# TopSchem.net
KiCad netlist of a schematic drawn in EAGLE
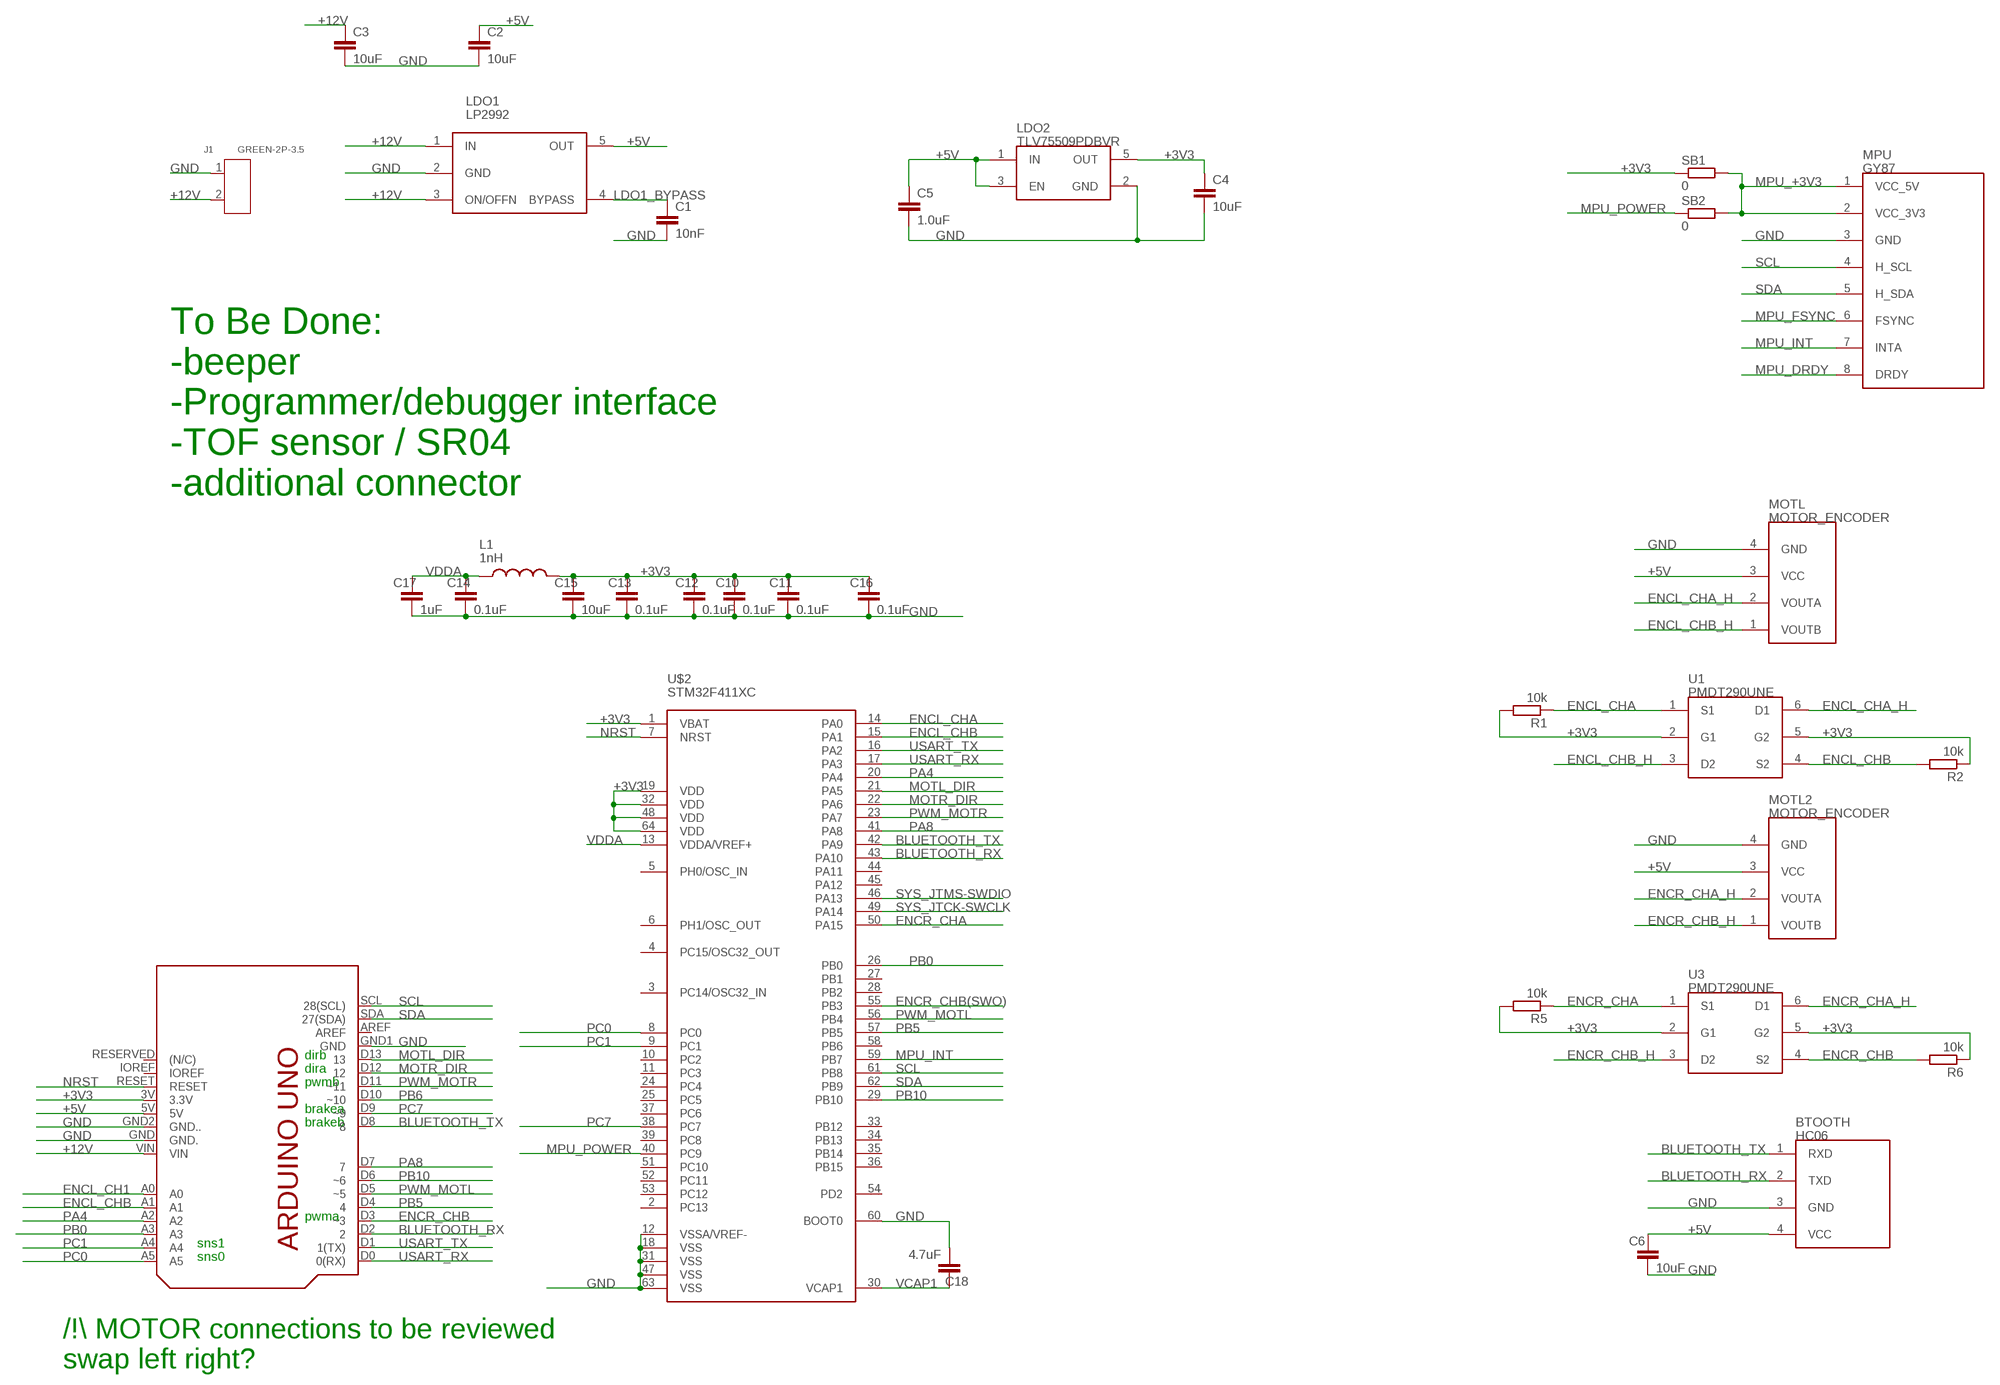
[diagram p0: schematic, sheet 1]

(export (version "E")
  (design (tool "Eeschema 10.0.6"))
  (components
    (comp (ref "BTOOTH")
      (value "HC06")
      (footprint "eagle-import:HC06")
      (libsource (lib "eagle-import") (part "HC06HC06"))
    )
    (comp (ref "C1")
      (value "10nF")
      (footprint "eagle-import:0603")
      (libsource (lib "eagle-import") (part "10NF-0603-50V-10%"))
    )
    (comp (ref "C2")
      (value "10uF")
      (footprint "eagle-import:0603")
      (libsource (lib "eagle-import") (part "10UF-0603-6.3V-20%"))
    )
    (comp (ref "C3")
      (value "10uF")
      (footprint "eagle-import:0603")
      (libsource (lib "eagle-import") (part "10UF-0603-6.3V-20%"))
    )
    (comp (ref "C4")
      (value "10uF")
      (footprint "eagle-import:0603")
      (libsource (lib "eagle-import") (part "10UF-0603-6.3V-20%"))
    )
    (comp (ref "C5")
      (value "1.0uF")
      (footprint "eagle-import:0603")
      (libsource (lib "eagle-import") (part "1.0UF-0603-16V-10%"))
    )
    (comp (ref "C6")
      (value "10uF")
      (footprint "eagle-import:0603")
      (libsource (lib "eagle-import") (part "0.1UF-0603-25V-(+80/-20%)"))
    )
    (comp (ref "C10")
      (value "0.1uF")
      (footprint "eagle-import:0603")
      (libsource (lib "eagle-import") (part "0.1UF-0603-25V-(+80/-20%)"))
    )
    (comp (ref "C11")
      (value "0.1uF")
      (footprint "eagle-import:0603")
      (libsource (lib "eagle-import") (part "0.1UF-0603-25V-(+80/-20%)"))
    )
    (comp (ref "C12")
      (value "0.1uF")
      (footprint "eagle-import:0603")
      (libsource (lib "eagle-import") (part "0.1UF-0603-25V-(+80/-20%)"))
    )
    (comp (ref "C13")
      (value "0.1uF")
      (footprint "eagle-import:0603")
      (libsource (lib "eagle-import") (part "0.1UF-0603-25V-(+80/-20%)"))
    )
    (comp (ref "C14")
      (value "0.1uF")
      (footprint "eagle-import:0603")
      (libsource (lib "eagle-import") (part "0.1UF-0603-25V-(+80/-20%)"))
    )
    (comp (ref "C15")
      (value "10uF")
      (footprint "eagle-import:0603")
      (libsource (lib "eagle-import") (part "0.1UF-0603-25V-(+80/-20%)"))
    )
    (comp (ref "C16")
      (value "0.1uF")
      (footprint "eagle-import:0603")
      (libsource (lib "eagle-import") (part "0.1UF-0603-25V-(+80/-20%)"))
    )
    (comp (ref "C17")
      (value "1uF")
      (footprint "eagle-import:0603")
      (libsource (lib "eagle-import") (part "0.1UF-0603-25V-(+80/-20%)"))
    )
    (comp (ref "C18")
      (value "4.7uF")
      (footprint "eagle-import:0603")
      (libsource (lib "eagle-import") (part "0.1UF-0603-25V-(+80/-20%)"))
    )
    (comp (ref "J1")
      (value "GREEN-2P-3.5")
      (footprint "eagle-import:H2-3.5-7.0X7.0MM")
      (libsource (lib "eagle-import") (part "SCREW-TERMINAL-GREEN(2P-3.5)"))
    )
    (comp (ref "L1")
      (value "1nH")
      (footprint "eagle-import:C0603")
      (libsource (lib "eagle-import") (part "INDUCTORC0603"))
    )
    (comp (ref "LDO1")
      (value "LP2992")
      (footprint "eagle-import:WE-TVS_SOT23-5L")
      (libsource (lib "eagle-import") (part "LP2992SOT23-5L"))
    )
    (comp (ref "LDO2")
      (value "TLV75509PDBVR")
      (footprint "eagle-import:WE-TVS_SOT23-5L")
      (libsource (lib "eagle-import") (part "TLV755P"))
    )
    (comp (ref "MOTL")
      (value "MOTOR_ENCODER")
      (footprint "eagle-import:ENCODER")
      (libsource (lib "eagle-import") (part "MOTOR_ENCODER"))
    )
    (comp (ref "MOTL2")
      (value "MOTOR_ENCODER")
      (footprint "eagle-import:ENCODER")
      (libsource (lib "eagle-import") (part "MOTOR_ENCODER"))
    )
    (comp (ref "MPU")
      (value "GY87")
      (footprint "eagle-import:SIP8")
      (libsource (lib "eagle-import") (part "GY87GY87"))
    )
    (comp (ref "R1")
      (value "10k")
      (footprint "eagle-import:R0603")
      (libsource (lib "eagle-import") (part "R-EU_R0603"))
    )
    (comp (ref "R2")
      (value "10k")
      (footprint "eagle-import:R0603")
      (libsource (lib "eagle-import") (part "R-EU_R0603"))
    )
    (comp (ref "R5")
      (value "10k")
      (footprint "eagle-import:R0603")
      (libsource (lib "eagle-import") (part "R-EU_R0603"))
    )
    (comp (ref "R6")
      (value "10k")
      (footprint "eagle-import:R0603")
      (libsource (lib "eagle-import") (part "R-EU_R0603"))
    )
    (comp (ref "SB1")
      (value "0")
      (footprint "eagle-import:R0603")
      (libsource (lib "eagle-import") (part "R-EU_R0603"))
    )
    (comp (ref "SB2")
      (value "0")
      (footprint "eagle-import:R0603")
      (libsource (lib "eagle-import") (part "R-EU_R0603"))
    )
    (comp (ref "SHIELD")
      (value "ARDUINO_UNO_EXTARDUINO_R3")
      (footprint "eagle-import:ARDUINOR3")
      (libsource (lib "eagle-import") (part "ARDUINO_UNO_EXTARDUINO_R3"))
    )
    (comp (ref "U$2")
      (value "STM32F411XC")
      (footprint "eagle-import:LQFP64")
      (libsource (lib "eagle-import") (part "STM32F411XC"))
    )
    (comp (ref "U1")
      (value "PMDT290UNE")
      (footprint "eagle-import:SOT666")
      (libsource (lib "eagle-import") (part "PMDT290UNESOT666"))
    )
    (comp (ref "U3")
      (value "PMDT290UNE")
      (footprint "eagle-import:SOT666")
      (libsource (lib "eagle-import") (part "PMDT290UNESOT666"))
    )
  )
  (nets
    (net (code "1") (name "/+3V3") (class "Default")
      (node (ref "C10") (pin "1") (pinfunction "1_1") (pintype "passive"))
      (node (ref "C11") (pin "1") (pinfunction "1_1") (pintype "passive"))
      (node (ref "C12") (pin "1") (pinfunction "1_1") (pintype "passive"))
      (node (ref "C13") (pin "1") (pinfunction "1_1") (pintype "passive"))
      (node (ref "C15") (pin "1") (pinfunction "1_1") (pintype "passive"))
      (node (ref "C16") (pin "1") (pinfunction "1_1") (pintype "passive"))
      (node (ref "C4") (pin "1") (pinfunction "1_1") (pintype "passive"))
      (node (ref "L1") (pin "2") (pinfunction "2_2") (pintype "passive"))
      (node (ref "LDO2") (pin "5") (pinfunction "OUT_5") (pintype "power_in"))
      (node (ref "R1") (pin "2") (pinfunction "2_2") (pintype "passive"))
      (node (ref "R2") (pin "1") (pinfunction "1_1") (pintype "passive"))
      (node (ref "R5") (pin "2") (pinfunction "2_2") (pintype "passive"))
      (node (ref "R6") (pin "1") (pinfunction "1_1") (pintype "passive"))
      (node (ref "SB1") (pin "1") (pinfunction "1_1") (pintype "passive"))
      (node (ref "SHIELD") (pin "3V") (pinfunction "3.3V_3V") (pintype "bidirectional"))
      (node (ref "U$2") (pin "1") (pinfunction "VBAT_1") (pintype "bidirectional"))
      (node (ref "U$2") (pin "19") (pinfunction "VDD_19") (pintype "bidirectional"))
      (node (ref "U$2") (pin "32") (pinfunction "VDD_32") (pintype "bidirectional"))
      (node (ref "U$2") (pin "48") (pinfunction "VDD_48") (pintype "bidirectional"))
      (node (ref "U$2") (pin "64") (pinfunction "VDD_64") (pintype "bidirectional"))
      (node (ref "U1") (pin "2") (pinfunction "G1_2") (pintype "input"))
      (node (ref "U1") (pin "5") (pinfunction "G2_5") (pintype "input"))
      (node (ref "U3") (pin "2") (pinfunction "G1_2") (pintype "input"))
      (node (ref "U3") (pin "5") (pinfunction "G2_5") (pintype "input"))
    )
    (net (code "2") (name "/+5V") (class "Default")
      (node (ref "BTOOTH") (pin "4") (pinfunction "VCC_4") (pintype "power_in"))
      (node (ref "C2") (pin "1") (pinfunction "1_1") (pintype "passive"))
      (node (ref "C5") (pin "1") (pinfunction "1_1") (pintype "passive"))
      (node (ref "C6") (pin "1") (pinfunction "1_1") (pintype "passive"))
      (node (ref "LDO1") (pin "5") (pinfunction "OUT_5") (pintype "power_in"))
      (node (ref "LDO2") (pin "1") (pinfunction "IN_1") (pintype "power_in"))
      (node (ref "LDO2") (pin "3") (pinfunction "EN_3") (pintype "input"))
      (node (ref "MOTL") (pin "3") (pinfunction "VCC_3") (pintype "power_in"))
      (node (ref "MOTL2") (pin "3") (pinfunction "VCC_3") (pintype "power_in"))
      (node (ref "SHIELD") (pin "5V") (pinfunction "5V_5V") (pintype "bidirectional"))
    )
    (net (code "3") (name "/+12V") (class "Default")
      (node (ref "C3") (pin "1") (pinfunction "1_1") (pintype "passive"))
      (node (ref "J1") (pin "2") (pinfunction "2_2") (pintype "bidirectional"))
      (node (ref "LDO1") (pin "1") (pinfunction "IN_1") (pintype "power_in"))
      (node (ref "LDO1") (pin "3") (pinfunction "ON/OFFN_3") (pintype "input"))
      (node (ref "SHIELD") (pin "VIN") (pinfunction "VIN_VIN") (pintype "bidirectional"))
    )
    (net (code "4") (name "/BLUETOOTH_RX") (class "Default")
      (node (ref "BTOOTH") (pin "2") (pinfunction "TXD_2") (pintype "input"))
      (node (ref "SHIELD") (pin "D2") (pinfunction "2_D2") (pintype "bidirectional"))
      (node (ref "U$2") (pin "43") (pinfunction "PA10_43") (pintype "bidirectional"))
    )
    (net (code "5") (name "/BLUETOOTH_TX") (class "Default")
      (node (ref "BTOOTH") (pin "1") (pinfunction "RXD_1") (pintype "output"))
      (node (ref "SHIELD") (pin "D8") (pinfunction "8_D8") (pintype "bidirectional"))
      (node (ref "U$2") (pin "42") (pinfunction "PA9_42") (pintype "bidirectional"))
    )
    (net (code "6") (name "/ENCL_CH1") (class "Default")
      (node (ref "SHIELD") (pin "A0") (pinfunction "A0_A0") (pintype "bidirectional"))
    )
    (net (code "7") (name "/ENCL_CHA") (class "Default")
      (node (ref "R1") (pin "1") (pinfunction "1_1") (pintype "passive"))
      (node (ref "U$2") (pin "14") (pinfunction "PA0_14") (pintype "bidirectional"))
      (node (ref "U1") (pin "1") (pinfunction "S1_1") (pintype "bidirectional"))
    )
    (net (code "8") (name "/ENCL_CHA_H") (class "Default")
      (node (ref "MOTL") (pin "2") (pinfunction "VOUTA_2") (pintype "bidirectional"))
      (node (ref "U1") (pin "6") (pinfunction "D1_6") (pintype "bidirectional"))
    )
    (net (code "9") (name "/ENCL_CHB") (class "Default")
      (node (ref "R2") (pin "2") (pinfunction "2_2") (pintype "passive"))
      (node (ref "SHIELD") (pin "A1") (pinfunction "A1_A1") (pintype "bidirectional"))
      (node (ref "U$2") (pin "15") (pinfunction "PA1_15") (pintype "bidirectional"))
      (node (ref "U1") (pin "4") (pinfunction "S2_4") (pintype "bidirectional"))
    )
    (net (code "10") (name "/ENCL_CHB_H") (class "Default")
      (node (ref "MOTL") (pin "1") (pinfunction "VOUTB_1") (pintype "bidirectional"))
      (node (ref "U1") (pin "3") (pinfunction "D2_3") (pintype "bidirectional"))
    )
    (net (code "11") (name "/ENCR_CHA") (class "Default")
      (node (ref "R5") (pin "1") (pinfunction "1_1") (pintype "passive"))
      (node (ref "U$2") (pin "50") (pinfunction "PA15_50") (pintype "bidirectional"))
      (node (ref "U3") (pin "1") (pinfunction "S1_1") (pintype "bidirectional"))
    )
    (net (code "12") (name "/ENCR_CHA_H") (class "Default")
      (node (ref "MOTL2") (pin "2") (pinfunction "VOUTA_2") (pintype "bidirectional"))
      (node (ref "U3") (pin "6") (pinfunction "D1_6") (pintype "bidirectional"))
    )
    (net (code "13") (name "/ENCR_CHB") (class "Default")
      (node (ref "R6") (pin "2") (pinfunction "2_2") (pintype "passive"))
      (node (ref "SHIELD") (pin "D3") (pinfunction "~{3}_D3") (pintype "bidirectional"))
      (node (ref "U3") (pin "4") (pinfunction "S2_4") (pintype "bidirectional"))
    )
    (net (code "14") (name "/ENCR_CHB(SWO)") (class "Default")
      (node (ref "U$2") (pin "55") (pinfunction "PB3_55") (pintype "bidirectional"))
    )
    (net (code "15") (name "/ENCR_CHB_H") (class "Default")
      (node (ref "MOTL2") (pin "1") (pinfunction "VOUTB_1") (pintype "bidirectional"))
      (node (ref "U3") (pin "3") (pinfunction "D2_3") (pintype "bidirectional"))
    )
    (net (code "16") (name "/GND") (class "Default")
      (node (ref "BTOOTH") (pin "3") (pinfunction "GND_3") (pintype "power_in"))
      (node (ref "C1") (pin "2") (pinfunction "2_2") (pintype "passive"))
      (node (ref "C10") (pin "2") (pinfunction "2_2") (pintype "passive"))
      (node (ref "C11") (pin "2") (pinfunction "2_2") (pintype "passive"))
      (node (ref "C12") (pin "2") (pinfunction "2_2") (pintype "passive"))
      (node (ref "C13") (pin "2") (pinfunction "2_2") (pintype "passive"))
      (node (ref "C14") (pin "2") (pinfunction "2_2") (pintype "passive"))
      (node (ref "C15") (pin "2") (pinfunction "2_2") (pintype "passive"))
      (node (ref "C16") (pin "2") (pinfunction "2_2") (pintype "passive"))
      (node (ref "C17") (pin "2") (pinfunction "2_2") (pintype "passive"))
      (node (ref "C18") (pin "2") (pinfunction "2_2") (pintype "passive"))
      (node (ref "C2") (pin "2") (pinfunction "2_2") (pintype "passive"))
      (node (ref "C3") (pin "2") (pinfunction "2_2") (pintype "passive"))
      (node (ref "C4") (pin "2") (pinfunction "2_2") (pintype "passive"))
      (node (ref "C5") (pin "2") (pinfunction "2_2") (pintype "passive"))
      (node (ref "C6") (pin "2") (pinfunction "2_2") (pintype "passive"))
      (node (ref "J1") (pin "1") (pinfunction "1_1") (pintype "bidirectional"))
      (node (ref "LDO1") (pin "2") (pinfunction "GND_2") (pintype "power_in"))
      (node (ref "LDO2") (pin "2") (pinfunction "GND_2") (pintype "power_in"))
      (node (ref "MOTL") (pin "4") (pinfunction "GND_4") (pintype "power_in"))
      (node (ref "MOTL2") (pin "4") (pinfunction "GND_4") (pintype "power_in"))
      (node (ref "MPU") (pin "3") (pinfunction "GND_3") (pintype "power_in"))
      (node (ref "SHIELD") (pin "GND") (pinfunction "GND._GND") (pintype "bidirectional"))
      (node (ref "SHIELD") (pin "GND1") (pinfunction "GND_GND1") (pintype "bidirectional"))
      (node (ref "SHIELD") (pin "GND2") (pinfunction "GND.._GND2") (pintype "bidirectional"))
      (node (ref "U$2") (pin "12") (pinfunction "VSSA/VREF-_12") (pintype "bidirectional"))
      (node (ref "U$2") (pin "18") (pinfunction "VSS_18") (pintype "bidirectional"))
      (node (ref "U$2") (pin "31") (pinfunction "VSS_31") (pintype "bidirectional"))
      (node (ref "U$2") (pin "47") (pinfunction "VSS_47") (pintype "bidirectional"))
      (node (ref "U$2") (pin "60") (pinfunction "BOOT0_60") (pintype "bidirectional"))
      (node (ref "U$2") (pin "63") (pinfunction "VSS_63") (pintype "bidirectional"))
    )
    (net (code "17") (name "/LDO1_BYPASS") (class "Default")
      (node (ref "C1") (pin "1") (pinfunction "1_1") (pintype "passive"))
      (node (ref "LDO1") (pin "4") (pinfunction "BYPASS_4") (pintype "output"))
    )
    (net (code "18") (name "/MOTL_DIR") (class "Default")
      (node (ref "SHIELD") (pin "D13") (pinfunction "13_D13") (pintype "bidirectional"))
      (node (ref "U$2") (pin "21") (pinfunction "PA5_21") (pintype "bidirectional"))
    )
    (net (code "19") (name "/MOTR_DIR") (class "Default")
      (node (ref "SHIELD") (pin "D12") (pinfunction "12_D12") (pintype "bidirectional"))
      (node (ref "U$2") (pin "22") (pinfunction "PA6_22") (pintype "bidirectional"))
    )
    (net (code "20") (name "/MPU_+3V3") (class "Default")
      (node (ref "MPU") (pin "1") (pinfunction "VCC_5V_1") (pintype "power_in"))
      (node (ref "MPU") (pin "2") (pinfunction "VCC_3V3_2") (pintype "power_in"))
      (node (ref "SB1") (pin "2") (pinfunction "2_2") (pintype "passive"))
      (node (ref "SB2") (pin "2") (pinfunction "2_2") (pintype "passive"))
    )
    (net (code "21") (name "/MPU_DRDY") (class "Default")
      (node (ref "MPU") (pin "8") (pinfunction "DRDY_8") (pintype "bidirectional"))
    )
    (net (code "22") (name "/MPU_FSYNC") (class "Default")
      (node (ref "MPU") (pin "6") (pinfunction "FSYNC_6") (pintype "bidirectional"))
    )
    (net (code "23") (name "/MPU_INT") (class "Default")
      (node (ref "MPU") (pin "7") (pinfunction "INTA_7") (pintype "bidirectional"))
      (node (ref "U$2") (pin "59") (pinfunction "PB7_59") (pintype "bidirectional"))
    )
    (net (code "24") (name "/MPU_POWER") (class "Default")
      (node (ref "SB2") (pin "1") (pinfunction "1_1") (pintype "passive"))
      (node (ref "U$2") (pin "40") (pinfunction "PC9_40") (pintype "bidirectional"))
    )
    (net (code "25") (name "/NRST") (class "Default")
      (node (ref "SHIELD") (pin "RESET") (pinfunction "RESET_RESET") (pintype "bidirectional"))
      (node (ref "U$2") (pin "7") (pinfunction "NRST_7") (pintype "bidirectional"))
    )
    (net (code "26") (name "/PA4") (class "Default")
      (node (ref "SHIELD") (pin "A2") (pinfunction "A2_A2") (pintype "bidirectional"))
      (node (ref "U$2") (pin "20") (pinfunction "PA4_20") (pintype "bidirectional"))
    )
    (net (code "27") (name "/PA8") (class "Default")
      (node (ref "SHIELD") (pin "D7") (pinfunction "7_D7") (pintype "bidirectional"))
      (node (ref "U$2") (pin "41") (pinfunction "PA8_41") (pintype "bidirectional"))
    )
    (net (code "28") (name "/PB0") (class "Default")
      (node (ref "SHIELD") (pin "A3") (pinfunction "A3_A3") (pintype "bidirectional"))
      (node (ref "U$2") (pin "26") (pinfunction "PB0_26") (pintype "bidirectional"))
    )
    (net (code "29") (name "/PB5") (class "Default")
      (node (ref "SHIELD") (pin "D4") (pinfunction "4_D4") (pintype "bidirectional"))
      (node (ref "U$2") (pin "57") (pinfunction "PB5_57") (pintype "bidirectional"))
    )
    (net (code "30") (name "/PB6") (class "Default")
      (node (ref "SHIELD") (pin "D10") (pinfunction "~{10}_D10") (pintype "bidirectional"))
    )
    (net (code "31") (name "/PB10") (class "Default")
      (node (ref "SHIELD") (pin "D6") (pinfunction "~{6}_D6") (pintype "bidirectional"))
      (node (ref "U$2") (pin "29") (pinfunction "PB10_29") (pintype "bidirectional"))
    )
    (net (code "32") (name "/PC0") (class "Default")
      (node (ref "SHIELD") (pin "A5") (pinfunction "A5_A5") (pintype "bidirectional"))
      (node (ref "U$2") (pin "8") (pinfunction "PC0_8") (pintype "bidirectional"))
    )
    (net (code "33") (name "/PC1") (class "Default")
      (node (ref "SHIELD") (pin "A4") (pinfunction "A4_A4") (pintype "bidirectional"))
      (node (ref "U$2") (pin "9") (pinfunction "PC1_9") (pintype "bidirectional"))
    )
    (net (code "34") (name "/PC7") (class "Default")
      (node (ref "SHIELD") (pin "D9") (pinfunction "~{9}_D9") (pintype "bidirectional"))
      (node (ref "U$2") (pin "38") (pinfunction "PC7_38") (pintype "bidirectional"))
    )
    (net (code "35") (name "/PWM_MOTL") (class "Default")
      (node (ref "SHIELD") (pin "D5") (pinfunction "~{5}_D5") (pintype "bidirectional"))
      (node (ref "U$2") (pin "56") (pinfunction "PB4_56") (pintype "bidirectional"))
    )
    (net (code "36") (name "/PWM_MOTR") (class "Default")
      (node (ref "SHIELD") (pin "D11") (pinfunction "~{11}_D11") (pintype "bidirectional"))
      (node (ref "U$2") (pin "23") (pinfunction "PA7_23") (pintype "bidirectional"))
    )
    (net (code "37") (name "/SCL") (class "Default")
      (node (ref "MPU") (pin "4") (pinfunction "H_SCL_4") (pintype "bidirectional"))
      (node (ref "SHIELD") (pin "SCL") (pinfunction "28(SCL)_SCL") (pintype "bidirectional"))
      (node (ref "U$2") (pin "61") (pinfunction "PB8_61") (pintype "bidirectional"))
    )
    (net (code "38") (name "/SDA") (class "Default")
      (node (ref "MPU") (pin "5") (pinfunction "H_SDA_5") (pintype "bidirectional"))
      (node (ref "SHIELD") (pin "SDA") (pinfunction "27(SDA)_SDA") (pintype "bidirectional"))
      (node (ref "U$2") (pin "62") (pinfunction "PB9_62") (pintype "bidirectional"))
    )
    (net (code "39") (name "/SYS_JTCK-SWCLK") (class "Default")
      (node (ref "U$2") (pin "49") (pinfunction "PA14_49") (pintype "bidirectional"))
    )
    (net (code "40") (name "/SYS_JTMS-SWDIO") (class "Default")
      (node (ref "U$2") (pin "46") (pinfunction "PA13_46") (pintype "bidirectional"))
    )
    (net (code "41") (name "/USART_RX") (class "Default")
      (node (ref "SHIELD") (pin "D0") (pinfunction "0(RX)_D0") (pintype "bidirectional"))
      (node (ref "U$2") (pin "17") (pinfunction "PA3_17") (pintype "bidirectional"))
    )
    (net (code "42") (name "/USART_TX") (class "Default")
      (node (ref "SHIELD") (pin "D1") (pinfunction "1(TX)_D1") (pintype "bidirectional"))
      (node (ref "U$2") (pin "16") (pinfunction "PA2_16") (pintype "bidirectional"))
    )
    (net (code "43") (name "/VCAP1") (class "Default")
      (node (ref "C18") (pin "1") (pinfunction "1_1") (pintype "passive"))
      (node (ref "U$2") (pin "30") (pinfunction "VCAP1_30") (pintype "bidirectional"))
    )
    (net (code "44") (name "/VDDA") (class "Default")
      (node (ref "C14") (pin "1") (pinfunction "1_1") (pintype "passive"))
      (node (ref "C17") (pin "1") (pinfunction "1_1") (pintype "passive"))
      (node (ref "L1") (pin "1") (pinfunction "1_1") (pintype "passive"))
      (node (ref "U$2") (pin "13") (pinfunction "VDDA/VREF+_13") (pintype "bidirectional"))
    )
    (net (code "45") (name "unconnected-(SHIELD-(N{slash}C)-PadRESERVED)") (class "Default")
      (node (ref "SHIELD") (pin "RESERVED") (pinfunction "(N/C)_RESERVED") (pintype "bidirectional"))
    )
    (net (code "46") (name "unconnected-(SHIELD-PadAREF)") (class "Default")
      (node (ref "SHIELD") (pin "AREF") (pinfunction "AREF_AREF") (pintype "bidirectional"))
    )
    (net (code "47") (name "unconnected-(SHIELD-PadIOREF)") (class "Default")
      (node (ref "SHIELD") (pin "IOREF") (pinfunction "IOREF_IOREF") (pintype "bidirectional"))
    )
    (net (code "48") (name "unconnected-(U$2-PA11-Pad44)") (class "Default")
      (node (ref "U$2") (pin "44") (pinfunction "PA11_44") (pintype "bidirectional"))
    )
    (net (code "49") (name "unconnected-(U$2-PA12-Pad45)") (class "Default")
      (node (ref "U$2") (pin "45") (pinfunction "PA12_45") (pintype "bidirectional"))
    )
    (net (code "50") (name "unconnected-(U$2-PB1-Pad27)") (class "Default")
      (node (ref "U$2") (pin "27") (pinfunction "PB1_27") (pintype "bidirectional"))
    )
    (net (code "51") (name "unconnected-(U$2-PB2-Pad28)") (class "Default")
      (node (ref "U$2") (pin "28") (pinfunction "PB2_28") (pintype "bidirectional"))
    )
    (net (code "52") (name "unconnected-(U$2-PB6-Pad58)") (class "Default")
      (node (ref "U$2") (pin "58") (pinfunction "PB6_58") (pintype "bidirectional"))
    )
    (net (code "53") (name "unconnected-(U$2-PB12-Pad33)") (class "Default")
      (node (ref "U$2") (pin "33") (pinfunction "PB12_33") (pintype "bidirectional"))
    )
    (net (code "54") (name "unconnected-(U$2-PB13-Pad34)") (class "Default")
      (node (ref "U$2") (pin "34") (pinfunction "PB13_34") (pintype "bidirectional"))
    )
    (net (code "55") (name "unconnected-(U$2-PB14-Pad35)") (class "Default")
      (node (ref "U$2") (pin "35") (pinfunction "PB14_35") (pintype "bidirectional"))
    )
    (net (code "56") (name "unconnected-(U$2-PB15-Pad36)") (class "Default")
      (node (ref "U$2") (pin "36") (pinfunction "PB15_36") (pintype "bidirectional"))
    )
    (net (code "57") (name "unconnected-(U$2-PC2-Pad10)") (class "Default")
      (node (ref "U$2") (pin "10") (pinfunction "PC2_10") (pintype "bidirectional"))
    )
    (net (code "58") (name "unconnected-(U$2-PC3-Pad11)") (class "Default")
      (node (ref "U$2") (pin "11") (pinfunction "PC3_11") (pintype "bidirectional"))
    )
    (net (code "59") (name "unconnected-(U$2-PC4-Pad24)") (class "Default")
      (node (ref "U$2") (pin "24") (pinfunction "PC4_24") (pintype "bidirectional"))
    )
    (net (code "60") (name "unconnected-(U$2-PC5-Pad25)") (class "Default")
      (node (ref "U$2") (pin "25") (pinfunction "PC5_25") (pintype "bidirectional"))
    )
    (net (code "61") (name "unconnected-(U$2-PC6-Pad37)") (class "Default")
      (node (ref "U$2") (pin "37") (pinfunction "PC6_37") (pintype "bidirectional"))
    )
    (net (code "62") (name "unconnected-(U$2-PC8-Pad39)") (class "Default")
      (node (ref "U$2") (pin "39") (pinfunction "PC8_39") (pintype "bidirectional"))
    )
    (net (code "63") (name "unconnected-(U$2-PC10-Pad51)") (class "Default")
      (node (ref "U$2") (pin "51") (pinfunction "PC10_51") (pintype "bidirectional"))
    )
    (net (code "64") (name "unconnected-(U$2-PC11-Pad52)") (class "Default")
      (node (ref "U$2") (pin "52") (pinfunction "PC11_52") (pintype "bidirectional"))
    )
    (net (code "65") (name "unconnected-(U$2-PC12-Pad53)") (class "Default")
      (node (ref "U$2") (pin "53") (pinfunction "PC12_53") (pintype "bidirectional"))
    )
    (net (code "66") (name "unconnected-(U$2-PC13-Pad2)") (class "Default")
      (node (ref "U$2") (pin "2") (pinfunction "PC13_2") (pintype "bidirectional"))
    )
    (net (code "67") (name "unconnected-(U$2-PC14{slash}OSC32_IN-Pad3)") (class "Default")
      (node (ref "U$2") (pin "3") (pinfunction "PC14/OSC32_IN_3") (pintype "bidirectional"))
    )
    (net (code "68") (name "unconnected-(U$2-PC15{slash}OSC32_OUT-Pad4)") (class "Default")
      (node (ref "U$2") (pin "4") (pinfunction "PC15/OSC32_OUT_4") (pintype "bidirectional"))
    )
    (net (code "69") (name "unconnected-(U$2-PD2-Pad54)") (class "Default")
      (node (ref "U$2") (pin "54") (pinfunction "PD2_54") (pintype "bidirectional"))
    )
    (net (code "70") (name "unconnected-(U$2-PH0{slash}OSC_IN-Pad5)") (class "Default")
      (node (ref "U$2") (pin "5") (pinfunction "PH0/OSC_IN_5") (pintype "bidirectional"))
    )
    (net (code "71") (name "unconnected-(U$2-PH1{slash}OSC_OUT-Pad6)") (class "Default")
      (node (ref "U$2") (pin "6") (pinfunction "PH1/OSC_OUT_6") (pintype "bidirectional"))
    )
  )
)
